# LCD_SD_Board.net
KiCad netlist of a schematic drawn in EAGLE
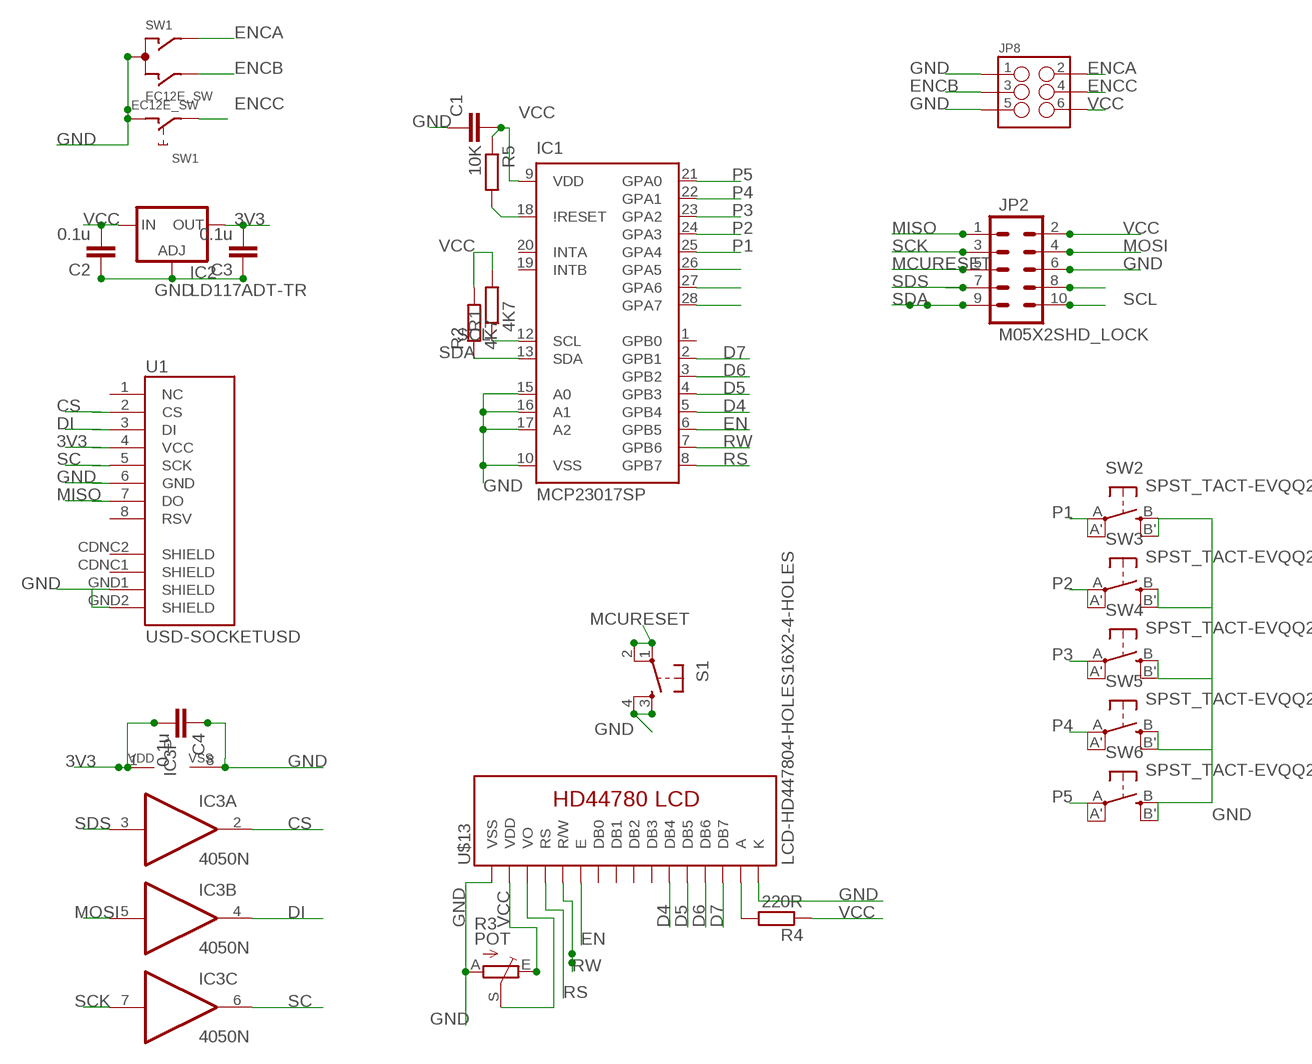
[diagram p0: schematic, sheet 2]

(export (version "E")
  (design (tool "Eeschema 10.0.6"))
  (components
    (comp (ref "C1")
      (value "CAP1206")
      (footprint "eagle-import:1206")
      (libsource (lib "eagle-import") (part "CAP1206"))
    )
    (comp (ref "C2")
      (value "0.1u")
      (footprint "eagle-import:1206")
      (libsource (lib "eagle-import") (part "CAP1206"))
    )
    (comp (ref "C3")
      (value "0.1u")
      (footprint "eagle-import:1206")
      (libsource (lib "eagle-import") (part "CAP1206"))
    )
    (comp (ref "C4")
      (value "0.1u")
      (footprint "eagle-import:1206")
      (libsource (lib "eagle-import") (part "CAP1206"))
    )
    (comp (ref "IC1")
      (value "MCP23017SP")
      (footprint "eagle-import:DIL28-3")
      (libsource (lib "eagle-import") (part "MCP23017SP"))
    )
    (comp (ref "IC2")
      (value "LD117ADT-TR")
      (footprint "eagle-import:DPACK")
      (libsource (lib "eagle-import") (part "LD117A?DT-TR"))
    )
    (comp (ref "IC3")
      (value "4050N")
      (footprint "eagle-import:DIL16")
      (libsource (lib "eagle-import") (part "4050N"))
    )
    (comp (ref "JP2")
      (value "M05X2SHD_LOCK")
      (footprint "eagle-import:2X5-SHROUDED_LOCK")
      (libsource (lib "eagle-import") (part "M05X2SHD_LOCK"))
    )
    (comp (ref "JP8")
      (value "M03X2SHROUD")
      (footprint "eagle-import:2X3-SHROUDED")
      (libsource (lib "eagle-import") (part "M03X2SHROUD"))
    )
    (comp (ref "R1")
      (value "4K7")
      (footprint "eagle-import:M1206")
      (libsource (lib "eagle-import") (part "R-EU_M1206"))
    )
    (comp (ref "R2")
      (value "4K7")
      (footprint "eagle-import:M1206")
      (libsource (lib "eagle-import") (part "R-EU_M1206"))
    )
    (comp (ref "R3")
      (value "POT")
      (footprint "eagle-import:CA9V")
      (libsource (lib "eagle-import") (part "TRIM_EU-CA9V"))
    )
    (comp (ref "R4")
      (value "220R")
      (footprint "eagle-import:M1206")
      (libsource (lib "eagle-import") (part "R-EU_M1206"))
    )
    (comp (ref "R5")
      (value "10K")
      (footprint "eagle-import:0204_7")
      (libsource (lib "eagle-import") (part "R-EU_0204/7"))
    )
    (comp (ref "S1")
      (value "TAC_SWITCHPTH")
      (footprint "eagle-import:TACTILE-PTH")
      (libsource (lib "eagle-import") (part "TAC_SWITCHPTH"))
    )
    (comp (ref "SW1")
      (value "EC12E_SW")
      (footprint "eagle-import:ALPS_EC12E_SW")
      (fields (field (name "MPN") "EC12E2424407"))
      (libsource (lib "eagle-import") (part "EC12E_SW"))
    )
    (comp (ref "SW2")
      (value "SPST_TACT-EVQQ2")
      (footprint "eagle-import:EVQ-Q2")
      (libsource (lib "eagle-import") (part "SPST_TACT-EVQQ2"))
    )
    (comp (ref "SW3")
      (value "SPST_TACT-EVQQ2")
      (footprint "eagle-import:EVQ-Q2")
      (libsource (lib "eagle-import") (part "SPST_TACT-EVQQ2"))
    )
    (comp (ref "SW4")
      (value "SPST_TACT-EVQQ2")
      (footprint "eagle-import:EVQ-Q2")
      (libsource (lib "eagle-import") (part "SPST_TACT-EVQQ2"))
    )
    (comp (ref "SW5")
      (value "SPST_TACT-EVQQ2")
      (footprint "eagle-import:EVQ-Q2")
      (libsource (lib "eagle-import") (part "SPST_TACT-EVQQ2"))
    )
    (comp (ref "SW6")
      (value "SPST_TACT-EVQQ2")
      (footprint "eagle-import:EVQ-Q2")
      (libsource (lib "eagle-import") (part "SPST_TACT-EVQQ2"))
    )
    (comp (ref "U$13")
      (value "LCD-HD447804-HOLES16X2-4-HOLES")
      (footprint "eagle-import:LCD-16X2-4HOLES")
      (libsource (lib "eagle-import") (part "LCD-HD4478016X2-4-HOLES4-HOLES"))
    )
    (comp (ref "U1")
      (value "USD-SOCKETUSD")
      (footprint "eagle-import:USD-SOCKET-PP")
      (libsource (lib "eagle-import") (part "USD-SOCKETUSD"))
    )
  )
  (nets
    (net (code "1") (name "3V3") (class "Default")
      (node (ref "C3") (pin "2") (pinfunction "2_2") (pintype "passive"))
      (node (ref "C4") (pin "2") (pinfunction "2_2") (pintype "passive"))
      (node (ref "IC2") (pin "4") (pinfunction "OUT_4") (pintype "passive"))
      (node (ref "IC3") (pin "1") (pinfunction "VDD_1") (pintype "power_in"))
      (node (ref "U1") (pin "4") (pinfunction "VCC_4") (pintype "bidirectional"))
    )
    (net (code "2") (name "CS") (class "Default")
      (node (ref "IC3") (pin "2") (pinfunction "O_2") (pintype "output"))
      (node (ref "U1") (pin "2") (pinfunction "CS_2") (pintype "bidirectional"))
    )
    (net (code "3") (name "D4") (class "Default")
      (node (ref "IC1") (pin "5") (pinfunction "GPB4_5") (pintype "bidirectional"))
      (node (ref "U$13") (pin "11") (pinfunction "DB4_11") (pintype "bidirectional"))
    )
    (net (code "4") (name "D5") (class "Default")
      (node (ref "IC1") (pin "4") (pinfunction "GPB3_4") (pintype "bidirectional"))
      (node (ref "U$13") (pin "12") (pinfunction "DB5_12") (pintype "bidirectional"))
    )
    (net (code "5") (name "D6") (class "Default")
      (node (ref "IC1") (pin "3") (pinfunction "GPB2_3") (pintype "bidirectional"))
      (node (ref "U$13") (pin "13") (pinfunction "DB6_13") (pintype "bidirectional"))
    )
    (net (code "6") (name "D7") (class "Default")
      (node (ref "IC1") (pin "2") (pinfunction "GPB1_2") (pintype "bidirectional"))
      (node (ref "U$13") (pin "14") (pinfunction "DB7_14") (pintype "bidirectional"))
    )
    (net (code "7") (name "DI") (class "Default")
      (node (ref "IC3") (pin "4") (pinfunction "O_4") (pintype "output"))
      (node (ref "U1") (pin "3") (pinfunction "DI_3") (pintype "bidirectional"))
    )
    (net (code "8") (name "EN") (class "Default")
      (node (ref "IC1") (pin "6") (pinfunction "GPB5_6") (pintype "bidirectional"))
      (node (ref "U$13") (pin "6") (pinfunction "E_6") (pintype "input"))
    )
    (net (code "9") (name "ENCA") (class "Default")
      (node (ref "JP8") (pin "2") (pinfunction "2_2") (pintype "bidirectional"))
      (node (ref "SW1") (pin "A") (pinfunction "A_A") (pintype "passive"))
    )
    (net (code "10") (name "ENCB") (class "Default")
      (node (ref "JP8") (pin "3") (pinfunction "3_3") (pintype "bidirectional"))
      (node (ref "SW1") (pin "B") (pinfunction "B_B") (pintype "passive"))
    )
    (net (code "11") (name "ENCC") (class "Default")
      (node (ref "JP8") (pin "4") (pinfunction "4_4") (pintype "bidirectional"))
      (node (ref "SW1") (pin "E") (pinfunction "2_E") (pintype "passive"))
    )
    (net (code "12") (name "GND") (class "Default")
      (node (ref "C1") (pin "1") (pinfunction "1_1") (pintype "passive"))
      (node (ref "C2") (pin "1") (pinfunction "1_1") (pintype "passive"))
      (node (ref "C3") (pin "1") (pinfunction "1_1") (pintype "passive"))
      (node (ref "C4") (pin "1") (pinfunction "1_1") (pintype "passive"))
      (node (ref "IC1") (pin "10") (pinfunction "VSS_10") (pintype "power_in"))
      (node (ref "IC1") (pin "15") (pinfunction "A0_15") (pintype "input"))
      (node (ref "IC1") (pin "16") (pinfunction "A1_16") (pintype "input"))
      (node (ref "IC1") (pin "17") (pinfunction "A2_17") (pintype "input"))
      (node (ref "IC2") (pin "1") (pinfunction "ADJ_1") (pintype "input"))
      (node (ref "IC3") (pin "8") (pinfunction "VSS_8") (pintype "power_in"))
      (node (ref "JP2") (pin "6") (pinfunction "6_6") (pintype "passive"))
      (node (ref "JP8") (pin "1") (pinfunction "1_1") (pintype "bidirectional"))
      (node (ref "JP8") (pin "5") (pinfunction "5_5") (pintype "bidirectional"))
      (node (ref "R3") (pin "A") (pinfunction "A_A") (pintype "passive"))
      (node (ref "S1") (pin "3") (pinfunction "3_3") (pintype "passive"))
      (node (ref "S1") (pin "4") (pinfunction "4_4") (pintype "passive"))
      (node (ref "SW1") (pin "C") (pinfunction "C_C") (pintype "passive"))
      (node (ref "SW1") (pin "D") (pinfunction "1_D") (pintype "passive"))
      (node (ref "SW2") (pin "B") (pinfunction "S_B") (pintype "passive"))
      (node (ref "SW2") (pin "B'") (pinfunction "S1_B'") (pintype "passive"))
      (node (ref "SW3") (pin "B") (pinfunction "S_B") (pintype "passive"))
      (node (ref "SW3") (pin "B'") (pinfunction "S1_B'") (pintype "passive"))
      (node (ref "SW4") (pin "B") (pinfunction "S_B") (pintype "passive"))
      (node (ref "SW4") (pin "B'") (pinfunction "S1_B'") (pintype "passive"))
      (node (ref "SW5") (pin "B") (pinfunction "S_B") (pintype "passive"))
      (node (ref "SW5") (pin "B'") (pinfunction "S1_B'") (pintype "passive"))
      (node (ref "SW6") (pin "B") (pinfunction "S_B") (pintype "passive"))
      (node (ref "SW6") (pin "B'") (pinfunction "S1_B'") (pintype "passive"))
      (node (ref "U$13") (pin "1") (pinfunction "VSS_1") (pintype "power_in"))
      (node (ref "U$13") (pin "16") (pinfunction "K_16") (pintype "power_in"))
      (node (ref "U1") (pin "6") (pinfunction "GND_6") (pintype "bidirectional"))
      (node (ref "U1") (pin "GND1") (pinfunction "SHIELD_GND1") (pintype "bidirectional"))
      (node (ref "U1") (pin "GND2") (pinfunction "SHIELD_GND2") (pintype "bidirectional"))
    )
    (net (code "13") (name "MCURESET") (class "Default")
      (node (ref "JP2") (pin "5") (pinfunction "5_5") (pintype "passive"))
      (node (ref "S1") (pin "1") (pinfunction "1_1") (pintype "passive"))
      (node (ref "S1") (pin "2") (pinfunction "2_2") (pintype "passive"))
    )
    (net (code "14") (name "MISO") (class "Default")
      (node (ref "JP2") (pin "1") (pinfunction "1_1") (pintype "passive"))
      (node (ref "U1") (pin "7") (pinfunction "DO_7") (pintype "bidirectional"))
    )
    (net (code "15") (name "MOSI") (class "Default")
      (node (ref "IC3") (pin "5") (pinfunction "I_5") (pintype "input"))
      (node (ref "JP2") (pin "4") (pinfunction "4_4") (pintype "passive"))
    )
    (net (code "16") (name "Net-(IC1-\\~{RESET})") (class "Default")
      (node (ref "IC1") (pin "18") (pinfunction "\\~{RESET}_18") (pintype "input"))
      (node (ref "R5") (pin "2") (pinfunction "2_2") (pintype "passive"))
    )
    (net (code "17") (name "Net-(U$13-A)") (class "Default")
      (node (ref "R4") (pin "2") (pinfunction "2_2") (pintype "passive"))
      (node (ref "U$13") (pin "15") (pinfunction "A_15") (pintype "power_in"))
    )
    (net (code "18") (name "Net-(U$13-VO)") (class "Default")
      (node (ref "R3") (pin "S") (pinfunction "S_S") (pintype "passive"))
      (node (ref "U$13") (pin "3") (pinfunction "VO_3") (pintype "bidirectional"))
    )
    (net (code "19") (name "P1") (class "Default")
      (node (ref "IC1") (pin "25") (pinfunction "GPA4_25") (pintype "bidirectional"))
      (node (ref "SW2") (pin "A") (pinfunction "P_A") (pintype "passive"))
      (node (ref "SW2") (pin "A'") (pinfunction "P1_A'") (pintype "passive"))
    )
    (net (code "20") (name "P2") (class "Default")
      (node (ref "IC1") (pin "24") (pinfunction "GPA3_24") (pintype "bidirectional"))
      (node (ref "SW3") (pin "A") (pinfunction "P_A") (pintype "passive"))
      (node (ref "SW3") (pin "A'") (pinfunction "P1_A'") (pintype "passive"))
    )
    (net (code "21") (name "P3") (class "Default")
      (node (ref "IC1") (pin "23") (pinfunction "GPA2_23") (pintype "bidirectional"))
      (node (ref "SW4") (pin "A") (pinfunction "P_A") (pintype "passive"))
      (node (ref "SW4") (pin "A'") (pinfunction "P1_A'") (pintype "passive"))
    )
    (net (code "22") (name "P4") (class "Default")
      (node (ref "IC1") (pin "22") (pinfunction "GPA1_22") (pintype "bidirectional"))
      (node (ref "SW5") (pin "A") (pinfunction "P_A") (pintype "passive"))
      (node (ref "SW5") (pin "A'") (pinfunction "P1_A'") (pintype "passive"))
    )
    (net (code "23") (name "P5") (class "Default")
      (node (ref "IC1") (pin "21") (pinfunction "GPA0_21") (pintype "bidirectional"))
      (node (ref "SW6") (pin "A") (pinfunction "P_A") (pintype "passive"))
      (node (ref "SW6") (pin "A'") (pinfunction "P1_A'") (pintype "passive"))
    )
    (net (code "24") (name "RS") (class "Default")
      (node (ref "IC1") (pin "8") (pinfunction "GPB7_8") (pintype "bidirectional"))
      (node (ref "U$13") (pin "4") (pinfunction "RS_4") (pintype "input"))
    )
    (net (code "25") (name "RW") (class "Default")
      (node (ref "IC1") (pin "7") (pinfunction "GPB6_7") (pintype "bidirectional"))
      (node (ref "U$13") (pin "5") (pinfunction "R/W_5") (pintype "input"))
    )
    (net (code "26") (name "SC") (class "Default")
      (node (ref "IC3") (pin "6") (pinfunction "O_6") (pintype "output"))
      (node (ref "U1") (pin "5") (pinfunction "SCK_5") (pintype "bidirectional"))
    )
    (net (code "27") (name "SCK") (class "Default")
      (node (ref "IC3") (pin "7") (pinfunction "I_7") (pintype "input"))
      (node (ref "JP2") (pin "3") (pinfunction "3_3") (pintype "passive"))
    )
    (net (code "28") (name "SCL") (class "Default")
      (node (ref "IC1") (pin "12") (pinfunction "SCL_12") (pintype "input"))
      (node (ref "JP2") (pin "10") (pinfunction "10_10") (pintype "passive"))
      (node (ref "R1") (pin "1") (pinfunction "1_1") (pintype "passive"))
    )
    (net (code "29") (name "SDA") (class "Default")
      (node (ref "IC1") (pin "13") (pinfunction "SDA_13") (pintype "bidirectional"))
      (node (ref "JP2") (pin "9") (pinfunction "9_9") (pintype "passive"))
      (node (ref "R2") (pin "1") (pinfunction "1_1") (pintype "passive"))
    )
    (net (code "30") (name "SDS") (class "Default")
      (node (ref "IC3") (pin "3") (pinfunction "I_3") (pintype "input"))
      (node (ref "JP2") (pin "7") (pinfunction "7_7") (pintype "passive"))
    )
    (net (code "31") (name "VCC") (class "Default")
      (node (ref "C1") (pin "2") (pinfunction "2_2") (pintype "passive"))
      (node (ref "C2") (pin "2") (pinfunction "2_2") (pintype "passive"))
      (node (ref "IC1") (pin "9") (pinfunction "VDD_9") (pintype "power_in"))
      (node (ref "IC2") (pin "3") (pinfunction "IN_3") (pintype "input"))
      (node (ref "JP2") (pin "2") (pinfunction "2_2") (pintype "passive"))
      (node (ref "JP8") (pin "6") (pinfunction "6_6") (pintype "bidirectional"))
      (node (ref "R1") (pin "2") (pinfunction "2_2") (pintype "passive"))
      (node (ref "R2") (pin "2") (pinfunction "2_2") (pintype "passive"))
      (node (ref "R3") (pin "E") (pinfunction "E_E") (pintype "passive"))
      (node (ref "R4") (pin "1") (pinfunction "1_1") (pintype "passive"))
      (node (ref "R5") (pin "1") (pinfunction "1_1") (pintype "passive"))
      (node (ref "U$13") (pin "2") (pinfunction "VDD_2") (pintype "power_in"))
    )
    (net (code "32") (name "unconnected-(IC1-GPA5-Pad26)") (class "Default")
      (node (ref "IC1") (pin "26") (pinfunction "GPA5_26") (pintype "bidirectional"))
    )
    (net (code "33") (name "unconnected-(IC1-GPA6-Pad27)") (class "Default")
      (node (ref "IC1") (pin "27") (pinfunction "GPA6_27") (pintype "bidirectional"))
    )
    (net (code "34") (name "unconnected-(IC1-GPA7-Pad28)") (class "Default")
      (node (ref "IC1") (pin "28") (pinfunction "GPA7_28") (pintype "bidirectional"))
    )
    (net (code "35") (name "unconnected-(IC1-GPB0-Pad1)") (class "Default")
      (node (ref "IC1") (pin "1") (pinfunction "GPB0_1") (pintype "bidirectional"))
    )
    (net (code "36") (name "unconnected-(IC1-INTA-Pad20)") (class "Default")
      (node (ref "IC1") (pin "20") (pinfunction "INTA_20") (pintype "output"))
    )
    (net (code "37") (name "unconnected-(IC1-INTB-Pad19)") (class "Default")
      (node (ref "IC1") (pin "19") (pinfunction "INTB_19") (pintype "output"))
    )
    (net (code "38") (name "unconnected-(JP2-Pad8)") (class "Default")
      (node (ref "JP2") (pin "8") (pinfunction "8_8") (pintype "passive"))
    )
    (net (code "39") (name "unconnected-(U$13-DB0-Pad7)") (class "Default")
      (node (ref "U$13") (pin "7") (pinfunction "DB0_7") (pintype "bidirectional"))
    )
    (net (code "40") (name "unconnected-(U$13-DB1-Pad8)") (class "Default")
      (node (ref "U$13") (pin "8") (pinfunction "DB1_8") (pintype "bidirectional"))
    )
    (net (code "41") (name "unconnected-(U$13-DB2-Pad9)") (class "Default")
      (node (ref "U$13") (pin "9") (pinfunction "DB2_9") (pintype "bidirectional"))
    )
    (net (code "42") (name "unconnected-(U$13-DB3-Pad10)") (class "Default")
      (node (ref "U$13") (pin "10") (pinfunction "DB3_10") (pintype "bidirectional"))
    )
    (net (code "43") (name "unconnected-(U1-NC-Pad1)") (class "Default")
      (node (ref "U1") (pin "1") (pinfunction "NC_1") (pintype "bidirectional"))
    )
    (net (code "44") (name "unconnected-(U1-RSV-Pad8)") (class "Default")
      (node (ref "U1") (pin "8") (pinfunction "RSV_8") (pintype "bidirectional"))
    )
    (net (code "45") (name "unconnected-(U1-SHIELD-PadCDNC1)") (class "Default")
      (node (ref "U1") (pin "CDNC1") (pinfunction "SHIELD_CDNC1") (pintype "bidirectional"))
    )
    (net (code "46") (name "unconnected-(U1-SHIELD-PadCDNC2)") (class "Default")
      (node (ref "U1") (pin "CDNC2") (pinfunction "SHIELD_CDNC2") (pintype "bidirectional"))
    )
  )
)
